# fets.net
KiCad netlist of a schematic drawn in Altium Designer
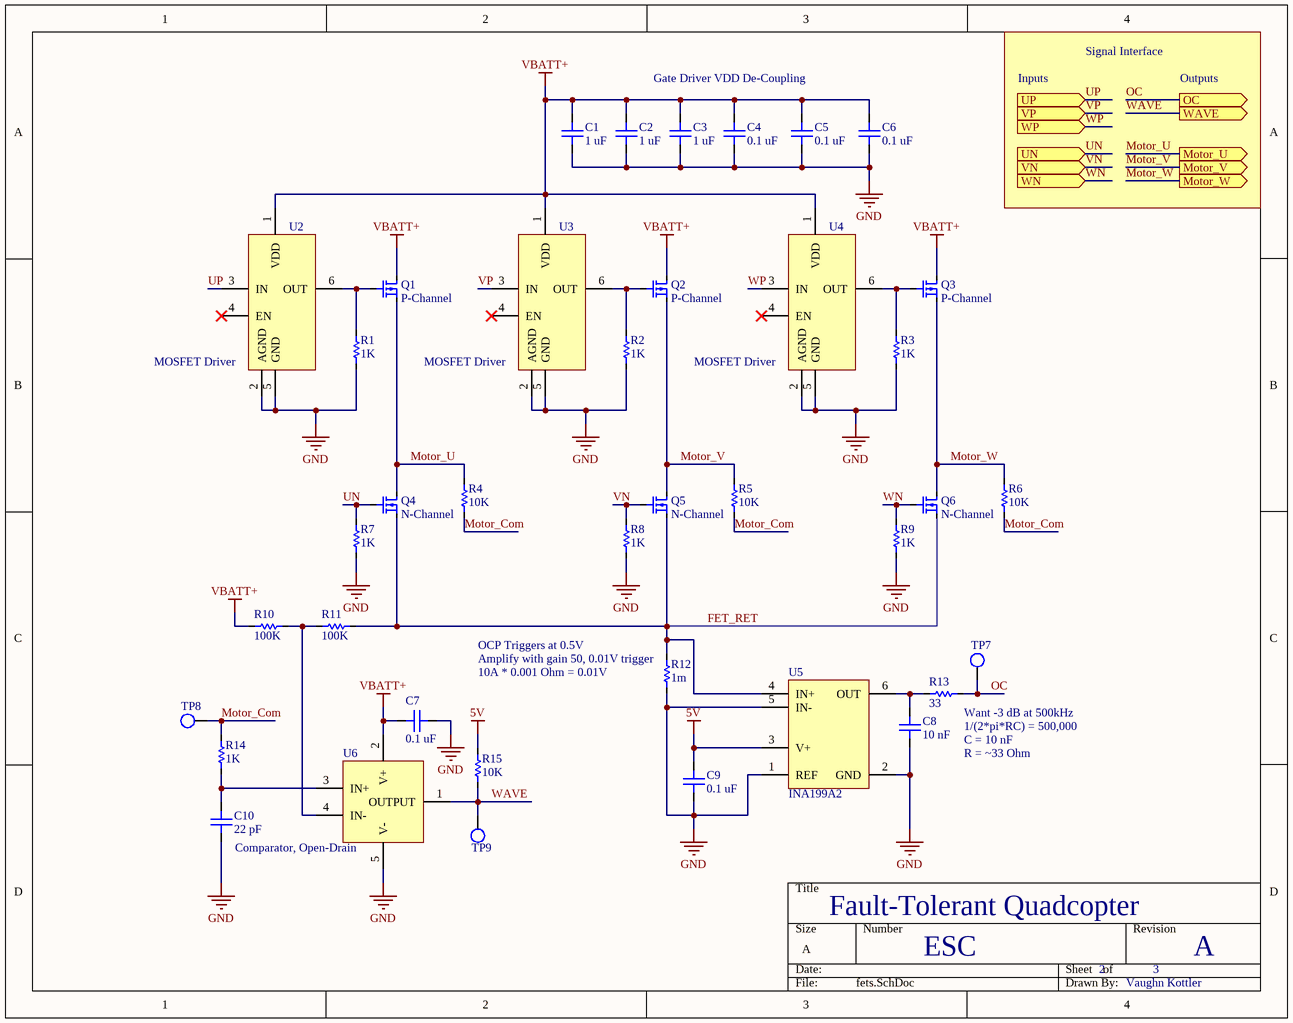
[diagram p0: fets.SchDoc]

(export (version "E")
  (design (tool "Eeschema 10.0.6"))
  (components
    (comp (ref "C1")
      (value "1 uF")
      (footprint "CAP-CER-0805-TALL")
      (description "10%, 0805")
      (libsource (lib "passive") (part "CAP-CER-1uF-10V"))
    )
    (comp (ref "C2")
      (value "1 uF")
      (footprint "CAP-CER-0805-TALL")
      (description "10%, 0805")
      (libsource (lib "passive") (part "CAP-CER-1uF-10V"))
    )
    (comp (ref "C3")
      (value "1 uF")
      (footprint "CAP-CER-0805-TALL")
      (description "10%, 0805")
      (libsource (lib "passive") (part "CAP-CER-1uF-10V"))
    )
    (comp (ref "C4")
      (value "0.1 uF")
      (footprint "CAP-CER-0805-SHORT")
      (description "10%, 0805")
      (libsource (lib "passive") (part "CAP-CER-0.1uF-25V"))
    )
    (comp (ref "C5")
      (value "0.1 uF")
      (footprint "CAP-CER-0805-SHORT")
      (description "10%, 0805")
      (libsource (lib "passive") (part "CAP-CER-0.1uF-25V"))
    )
    (comp (ref "C6")
      (value "0.1 uF")
      (footprint "CAP-CER-0805-SHORT")
      (description "10%, 0805")
      (libsource (lib "passive") (part "CAP-CER-0.1uF-25V"))
    )
    (comp (ref "C7")
      (value "0.1 uF")
      (footprint "CAP-CER-0805-SHORT")
      (description "10%, 0805")
      (libsource (lib "passive") (part "CAP-CER-0.1uF-25V"))
    )
    (comp (ref "C8")
      (value "10 nF")
      (footprint "CAP-CER-0805-SHORT")
      (description "10%, 0805")
      (libsource (lib "passive") (part "CAP-CER-10nF-50V"))
    )
    (comp (ref "C9")
      (value "0.1 uF")
      (footprint "CAP-CER-0805-SHORT")
      (description "10%, 0805")
      (libsource (lib "passive") (part "CAP-CER-0.1uF-25V"))
    )
    (comp (ref "C10")
      (value "22 pF")
      (footprint "CAP-CER-0805-SHORT")
      (description "±5%, 0805")
      (libsource (lib "passive") (part "CAP-CER-22pF-50V"))
    )
    (comp (ref "Q1")
      (value "P-Channel")
      (footprint "DPAK")
      (description "P-Channel MOSFET")
      (libsource (lib "ic") (part "PMOS-1.9VT-40VDS-40A"))
    )
    (comp (ref "Q2")
      (value "P-Channel")
      (footprint "DPAK")
      (description "P-Channel MOSFET")
      (libsource (lib "ic") (part "PMOS-1.9VT-40VDS-40A"))
    )
    (comp (ref "Q3")
      (value "P-Channel")
      (footprint "DPAK")
      (description "P-Channel MOSFET")
      (libsource (lib "ic") (part "PMOS-1.9VT-40VDS-40A"))
    )
    (comp (ref "Q4")
      (value "N-Channel")
      (footprint "DPAK")
      (description "N-Channel MOSFET")
      (libsource (lib "ic") (part "NMOS-2.5VT-60VDS-35A"))
    )
    (comp (ref "Q5")
      (value "N-Channel")
      (footprint "DPAK")
      (description "N-Channel MOSFET")
      (libsource (lib "ic") (part "NMOS-2.5VT-60VDS-35A"))
    )
    (comp (ref "Q6")
      (value "N-Channel")
      (footprint "DPAK")
      (description "N-Channel MOSFET")
      (libsource (lib "ic") (part "NMOS-2.5VT-60VDS-35A"))
    )
    (comp (ref "R1")
      (value "1K")
      (footprint "RES-0805")
      (description "0805")
      (libsource (lib "passive") (part "RES-1K-1/8W"))
    )
    (comp (ref "R2")
      (value "1K")
      (footprint "RES-0805")
      (description "0805")
      (libsource (lib "passive") (part "RES-1K-1/8W"))
    )
    (comp (ref "R3")
      (value "1K")
      (footprint "RES-0805")
      (description "0805")
      (libsource (lib "passive") (part "RES-1K-1/8W"))
    )
    (comp (ref "R4")
      (value "10K")
      (footprint "RES-0805")
      (description "0805")
      (libsource (lib "passive") (part "RES-10K-1/8W"))
    )
    (comp (ref "R5")
      (value "10K")
      (footprint "RES-0805")
      (description "0805")
      (libsource (lib "passive") (part "RES-10K-1/8W"))
    )
    (comp (ref "R6")
      (value "10K")
      (footprint "RES-0805")
      (description "0805")
      (libsource (lib "passive") (part "RES-10K-1/8W"))
    )
    (comp (ref "R7")
      (value "1K")
      (footprint "RES-0805")
      (description "0805")
      (libsource (lib "passive") (part "RES-1K-1/8W"))
    )
    (comp (ref "R8")
      (value "1K")
      (footprint "RES-0805")
      (description "0805")
      (libsource (lib "passive") (part "RES-1K-1/8W"))
    )
    (comp (ref "R9")
      (value "1K")
      (footprint "RES-0805")
      (description "0805")
      (libsource (lib "passive") (part "RES-1K-1/8W"))
    )
    (comp (ref "R10")
      (value "100K")
      (footprint "RES-0805")
      (description "0805")
      (libsource (lib "passive") (part "RES-100K-1/8W"))
    )
    (comp (ref "R11")
      (value "100K")
      (footprint "RES-0805")
      (description "0805")
      (libsource (lib "passive") (part "RES-100K-1/8W"))
    )
    (comp (ref "R12")
      (value "1m")
      (footprint "RES-1206")
      (description "0805")
      (libsource (lib "passive") (part "RES-1m-1W"))
    )
    (comp (ref "R13")
      (value "33")
      (footprint "RES-0805")
      (description "0805")
      (libsource (lib "passive") (part "RES-33-1/8W"))
    )
    (comp (ref "R14")
      (value "1K")
      (footprint "RES-0805")
      (description "0805")
      (libsource (lib "passive") (part "RES-1K-1/8W"))
    )
    (comp (ref "R15")
      (value "10K")
      (footprint "RES-0805")
      (description "0805")
      (libsource (lib "passive") (part "RES-10K-1/8W"))
    )
    (comp (ref "TP7")
      (value "Test Point")
      (footprint "0603 Test Point")
      (description "0603")
      (libsource (lib "passive") (part "Test Point"))
    )
    (comp (ref "TP8")
      (value "Test Point")
      (footprint "0603 Test Point")
      (description "0603")
      (libsource (lib "passive") (part "Test Point"))
    )
    (comp (ref "TP9")
      (value "Test Point")
      (footprint "0603 Test Point")
      (description "0603")
      (libsource (lib "passive") (part "Test Point"))
    )
    (comp (ref "U2")
      (value "MOSFET Driver")
      (footprint "SOT-23-6")
      (description "0.5A MOSFET Driver")
      (libsource (lib "ic") (part "MCP14A0052"))
    )
    (comp (ref "U3")
      (value "MOSFET Driver")
      (footprint "SOT-23-6")
      (description "0.5A MOSFET Driver")
      (libsource (lib "ic") (part "MCP14A0052"))
    )
    (comp (ref "U4")
      (value "MOSFET Driver")
      (footprint "SOT-23-6")
      (description "0.5A MOSFET Driver")
      (libsource (lib "ic") (part "MCP14A0052"))
    )
    (comp (ref "U5")
      (value "INA199A2")
      (footprint "SC70")
      (description "50 V/V, Current-Shunt Monitor")
      (libsource (lib "ic") (part "INA199A2"))
    )
    (comp (ref "U6")
      (value "Comparator, Open-Drain")
      (footprint "SOT-23-5")
      (libsource (lib "ic") (part "LMC7221"))
    )
  )
  (nets
    (net (code "1") (name "/FET_RET") (class "Default")
      (node (ref "Q4") (pin "3") (pinfunction "S_3") (pintype "passive"))
      (node (ref "Q5") (pin "3") (pinfunction "S_3") (pintype "passive"))
      (node (ref "Q6") (pin "3") (pinfunction "S_3") (pintype "passive"))
      (node (ref "R11") (pin "2") (pinfunction "2_2") (pintype "passive"))
      (node (ref "R12") (pin "1") (pinfunction "1_1") (pintype "passive"))
      (node (ref "U5") (pin "4") (pinfunction "IN+_4") (pintype "passive"))
    )
    (net (code "2") (name "/Motor_Com") (class "Default")
      (node (ref "R14") (pin "2") (pinfunction "2_2") (pintype "passive"))
      (node (ref "R4") (pin "1") (pinfunction "1_1") (pintype "passive"))
      (node (ref "R5") (pin "1") (pinfunction "1_1") (pintype "passive"))
      (node (ref "R6") (pin "1") (pinfunction "1_1") (pintype "passive"))
      (node (ref "TP8") (pin "1") (pinfunction "1_1") (pintype "passive"))
    )
    (net (code "3") (name "/Motor_U") (class "Default")
      (node (ref "Q1") (pin "3") (pinfunction "S_3") (pintype "passive"))
      (node (ref "Q4") (pin "2") (pinfunction "D_2") (pintype "passive"))
      (node (ref "R4") (pin "2") (pinfunction "2_2") (pintype "passive"))
    )
    (net (code "4") (name "/Motor_V") (class "Default")
      (node (ref "Q2") (pin "3") (pinfunction "S_3") (pintype "passive"))
      (node (ref "Q5") (pin "2") (pinfunction "D_2") (pintype "passive"))
      (node (ref "R5") (pin "2") (pinfunction "2_2") (pintype "passive"))
    )
    (net (code "5") (name "/Motor_W") (class "Default")
      (node (ref "Q3") (pin "3") (pinfunction "S_3") (pintype "passive"))
      (node (ref "Q6") (pin "2") (pinfunction "D_2") (pintype "passive"))
      (node (ref "R6") (pin "2") (pinfunction "2_2") (pintype "passive"))
    )
    (net (code "6") (name "/OC") (class "Default")
      (node (ref "R13") (pin "2") (pinfunction "2_2") (pintype "passive"))
      (node (ref "TP7") (pin "1") (pinfunction "1_1") (pintype "passive"))
    )
    (net (code "7") (name "/UN") (class "Default")
      (node (ref "Q4") (pin "1") (pinfunction "G_1") (pintype "passive"))
      (node (ref "R7") (pin "2") (pinfunction "2_2") (pintype "passive"))
    )
    (net (code "8") (name "/UP") (class "Default")
      (node (ref "U2") (pin "3") (pinfunction "IN_3") (pintype "passive"))
    )
    (net (code "9") (name "/VN") (class "Default")
      (node (ref "Q5") (pin "1") (pinfunction "G_1") (pintype "passive"))
      (node (ref "R8") (pin "2") (pinfunction "2_2") (pintype "passive"))
    )
    (net (code "10") (name "/VP") (class "Default")
      (node (ref "U3") (pin "3") (pinfunction "IN_3") (pintype "passive"))
    )
    (net (code "11") (name "/WAVE") (class "Default")
      (node (ref "R15") (pin "1") (pinfunction "1_1") (pintype "passive"))
      (node (ref "TP9") (pin "1") (pinfunction "1_1") (pintype "passive"))
      (node (ref "U6") (pin "1") (pinfunction "OUTPUT_1") (pintype "passive"))
    )
    (net (code "12") (name "/WN") (class "Default")
      (node (ref "Q6") (pin "1") (pinfunction "G_1") (pintype "passive"))
      (node (ref "R9") (pin "2") (pinfunction "2_2") (pintype "passive"))
    )
    (net (code "13") (name "/WP") (class "Default")
      (node (ref "U4") (pin "3") (pinfunction "IN_3") (pintype "passive"))
    )
    (net (code "14") (name "5V") (class "Default")
      (node (ref "C9") (pin "2") (pinfunction "2_2") (pintype "passive"))
      (node (ref "R15") (pin "2") (pinfunction "2_2") (pintype "passive"))
      (node (ref "U5") (pin "3") (pinfunction "V+_3") (pintype "passive"))
    )
    (net (code "15") (name "GND") (class "Default")
      (node (ref "C1") (pin "1") (pinfunction "1_1") (pintype "passive"))
      (node (ref "C10") (pin "1") (pinfunction "1_1") (pintype "passive"))
      (node (ref "C2") (pin "1") (pinfunction "1_1") (pintype "passive"))
      (node (ref "C3") (pin "1") (pinfunction "1_1") (pintype "passive"))
      (node (ref "C4") (pin "1") (pinfunction "1_1") (pintype "passive"))
      (node (ref "C5") (pin "1") (pinfunction "1_1") (pintype "passive"))
      (node (ref "C6") (pin "1") (pinfunction "1_1") (pintype "passive"))
      (node (ref "C7") (pin "1") (pinfunction "1_1") (pintype "passive"))
      (node (ref "C8") (pin "1") (pinfunction "1_1") (pintype "passive"))
      (node (ref "C9") (pin "1") (pinfunction "1_1") (pintype "passive"))
      (node (ref "R1") (pin "1") (pinfunction "1_1") (pintype "passive"))
      (node (ref "R12") (pin "2") (pinfunction "2_2") (pintype "passive"))
      (node (ref "R2") (pin "1") (pinfunction "1_1") (pintype "passive"))
      (node (ref "R3") (pin "1") (pinfunction "1_1") (pintype "passive"))
      (node (ref "R7") (pin "1") (pinfunction "1_1") (pintype "passive"))
      (node (ref "R8") (pin "1") (pinfunction "1_1") (pintype "passive"))
      (node (ref "R9") (pin "1") (pinfunction "1_1") (pintype "passive"))
      (node (ref "U2") (pin "2") (pinfunction "AGND_2") (pintype "passive"))
      (node (ref "U2") (pin "5") (pinfunction "GND_5") (pintype "passive"))
      (node (ref "U3") (pin "2") (pinfunction "AGND_2") (pintype "passive"))
      (node (ref "U3") (pin "5") (pinfunction "GND_5") (pintype "passive"))
      (node (ref "U4") (pin "2") (pinfunction "AGND_2") (pintype "passive"))
      (node (ref "U4") (pin "5") (pinfunction "GND_5") (pintype "passive"))
      (node (ref "U5") (pin "1") (pinfunction "REF_1") (pintype "passive"))
      (node (ref "U5") (pin "2") (pinfunction "GND_2") (pintype "passive"))
      (node (ref "U5") (pin "5") (pinfunction "IN-_5") (pintype "passive"))
      (node (ref "U6") (pin "5") (pinfunction "V-_5") (pintype "passive"))
    )
    (net (code "16") (name "Net-(Q1-G)") (class "Default")
      (node (ref "Q1") (pin "1") (pinfunction "G_1") (pintype "passive"))
      (node (ref "R1") (pin "2") (pinfunction "2_2") (pintype "passive"))
      (node (ref "U2") (pin "6") (pinfunction "OUT_6") (pintype "passive"))
    )
    (net (code "17") (name "Net-(Q2-G)") (class "Default")
      (node (ref "Q2") (pin "1") (pinfunction "G_1") (pintype "passive"))
      (node (ref "R2") (pin "2") (pinfunction "2_2") (pintype "passive"))
      (node (ref "U3") (pin "6") (pinfunction "OUT_6") (pintype "passive"))
    )
    (net (code "18") (name "Net-(Q3-G)") (class "Default")
      (node (ref "Q3") (pin "1") (pinfunction "G_1") (pintype "passive"))
      (node (ref "R3") (pin "2") (pinfunction "2_2") (pintype "passive"))
      (node (ref "U4") (pin "6") (pinfunction "OUT_6") (pintype "passive"))
    )
    (net (code "19") (name "Net-(U5-OUT)") (class "Default")
      (node (ref "C8") (pin "2") (pinfunction "2_2") (pintype "passive"))
      (node (ref "R13") (pin "1") (pinfunction "1_1") (pintype "passive"))
      (node (ref "U5") (pin "6") (pinfunction "OUT_6") (pintype "passive"))
    )
    (net (code "20") (name "Net-(U6-IN+)") (class "Default")
      (node (ref "C10") (pin "2") (pinfunction "2_2") (pintype "passive"))
      (node (ref "R14") (pin "1") (pinfunction "1_1") (pintype "passive"))
      (node (ref "U6") (pin "3") (pinfunction "IN+_3") (pintype "passive"))
    )
    (net (code "21") (name "Net-(U6-IN-)") (class "Default")
      (node (ref "R10") (pin "2") (pinfunction "2_2") (pintype "passive"))
      (node (ref "R11") (pin "1") (pinfunction "1_1") (pintype "passive"))
      (node (ref "U6") (pin "4") (pinfunction "IN-_4") (pintype "passive"))
    )
    (net (code "22") (name "VBATT+") (class "Default")
      (node (ref "C1") (pin "2") (pinfunction "2_2") (pintype "passive"))
      (node (ref "C2") (pin "2") (pinfunction "2_2") (pintype "passive"))
      (node (ref "C3") (pin "2") (pinfunction "2_2") (pintype "passive"))
      (node (ref "C4") (pin "2") (pinfunction "2_2") (pintype "passive"))
      (node (ref "C5") (pin "2") (pinfunction "2_2") (pintype "passive"))
      (node (ref "C6") (pin "2") (pinfunction "2_2") (pintype "passive"))
      (node (ref "C7") (pin "2") (pinfunction "2_2") (pintype "passive"))
      (node (ref "Q1") (pin "2") (pinfunction "D_2") (pintype "passive"))
      (node (ref "Q2") (pin "2") (pinfunction "D_2") (pintype "passive"))
      (node (ref "Q3") (pin "2") (pinfunction "D_2") (pintype "passive"))
      (node (ref "R10") (pin "1") (pinfunction "1_1") (pintype "passive"))
      (node (ref "U2") (pin "1") (pinfunction "VDD_1") (pintype "passive"))
      (node (ref "U3") (pin "1") (pinfunction "VDD_1") (pintype "passive"))
      (node (ref "U4") (pin "1") (pinfunction "VDD_1") (pintype "passive"))
      (node (ref "U6") (pin "2") (pinfunction "V+_2") (pintype "passive"))
    )
    (net (code "23") (name "unconnected-(U2-EN-Pad4)") (class "Default")
      (node (ref "U2") (pin "4") (pinfunction "EN_4") (pintype "passive+no_connect"))
    )
    (net (code "24") (name "unconnected-(U3-EN-Pad4)") (class "Default")
      (node (ref "U3") (pin "4") (pinfunction "EN_4") (pintype "passive+no_connect"))
    )
    (net (code "25") (name "unconnected-(U4-EN-Pad4)") (class "Default")
      (node (ref "U4") (pin "4") (pinfunction "EN_4") (pintype "passive+no_connect"))
    )
  )
)
